# qPCR_pcb_breakout_AD630ARZ.net
KiCad netlist of a schematic drawn in EAGLE
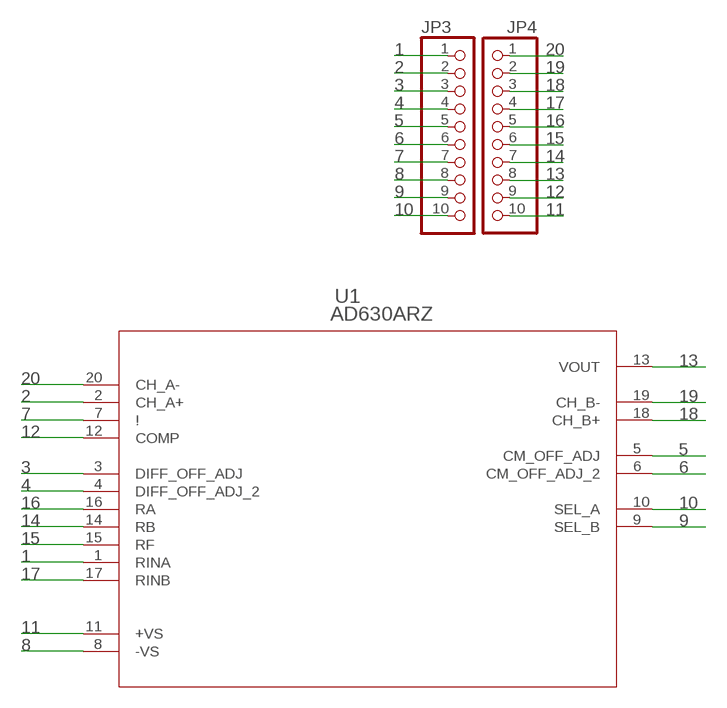
[diagram p0: schematic, sheet 1]

(export (version "E")
  (design (tool "Eeschema 10.0.6"))
  (components
    (comp (ref "JP3")
      (value "PINHD-1X10")
      (footprint "eagle-import:1X10")
      (libsource (lib "eagle-import") (part "PINHD-1X10"))
    )
    (comp (ref "JP4")
      (value "PINHD-1X10")
      (footprint "eagle-import:1X10")
      (libsource (lib "eagle-import") (part "PINHD-1X10"))
    )
    (comp (ref "U1")
      (value "AD630ARZ")
      (footprint "eagle-import:RW_20_ADI")
      (libsource (lib "eagle-import") (part "AD630ARZ"))
    )
  )
  (nets
    (net (code "1") (name "/1") (class "Default")
      (node (ref "JP3") (pin "1") (pinfunction "1_1") (pintype "passive"))
      (node (ref "U1") (pin "1") (pinfunction "RINA_1") (pintype "passive"))
    )
    (net (code "2") (name "/2") (class "Default")
      (node (ref "JP3") (pin "2") (pinfunction "2_2") (pintype "passive"))
      (node (ref "U1") (pin "2") (pinfunction "CH_A+_2") (pintype "passive"))
    )
    (net (code "3") (name "/3") (class "Default")
      (node (ref "JP3") (pin "3") (pinfunction "3_3") (pintype "passive"))
      (node (ref "U1") (pin "3") (pinfunction "DIFF_OFF_ADJ_3") (pintype "passive"))
    )
    (net (code "4") (name "/4") (class "Default")
      (node (ref "JP3") (pin "4") (pinfunction "4_4") (pintype "passive"))
      (node (ref "U1") (pin "4") (pinfunction "DIFF_OFF_ADJ_2_4") (pintype "passive"))
    )
    (net (code "5") (name "/5") (class "Default")
      (node (ref "JP3") (pin "5") (pinfunction "5_5") (pintype "passive"))
      (node (ref "U1") (pin "5") (pinfunction "CM_OFF_ADJ_5") (pintype "passive"))
    )
    (net (code "6") (name "/6") (class "Default")
      (node (ref "JP3") (pin "6") (pinfunction "6_6") (pintype "passive"))
      (node (ref "U1") (pin "6") (pinfunction "CM_OFF_ADJ_2_6") (pintype "passive"))
    )
    (net (code "7") (name "/7") (class "Default")
      (node (ref "JP3") (pin "7") (pinfunction "7_7") (pintype "passive"))
      (node (ref "U1") (pin "7") (pinfunction "~_7") (pintype "passive"))
    )
    (net (code "8") (name "/8") (class "Default")
      (node (ref "JP3") (pin "8") (pinfunction "8_8") (pintype "passive"))
      (node (ref "U1") (pin "8") (pinfunction "-VS_8") (pintype "power_in"))
    )
    (net (code "9") (name "/9") (class "Default")
      (node (ref "JP3") (pin "9") (pinfunction "9_9") (pintype "passive"))
      (node (ref "U1") (pin "9") (pinfunction "SEL_B_9") (pintype "passive"))
    )
    (net (code "10") (name "/10") (class "Default")
      (node (ref "JP3") (pin "10") (pinfunction "10_10") (pintype "passive"))
      (node (ref "U1") (pin "10") (pinfunction "SEL_A_10") (pintype "passive"))
    )
    (net (code "11") (name "/11") (class "Default")
      (node (ref "JP4") (pin "10") (pinfunction "10_10") (pintype "passive"))
      (node (ref "U1") (pin "11") (pinfunction "+VS_11") (pintype "power_in"))
    )
    (net (code "12") (name "/12") (class "Default")
      (node (ref "JP4") (pin "9") (pinfunction "9_9") (pintype "passive"))
      (node (ref "U1") (pin "12") (pinfunction "COMP_12") (pintype "passive"))
    )
    (net (code "13") (name "/13") (class "Default")
      (node (ref "JP4") (pin "8") (pinfunction "8_8") (pintype "passive"))
      (node (ref "U1") (pin "13") (pinfunction "VOUT_13") (pintype "passive"))
    )
    (net (code "14") (name "/14") (class "Default")
      (node (ref "JP4") (pin "7") (pinfunction "7_7") (pintype "passive"))
      (node (ref "U1") (pin "14") (pinfunction "RB_14") (pintype "passive"))
    )
    (net (code "15") (name "/15") (class "Default")
      (node (ref "JP4") (pin "6") (pinfunction "6_6") (pintype "passive"))
      (node (ref "U1") (pin "15") (pinfunction "RF_15") (pintype "passive"))
    )
    (net (code "16") (name "/16") (class "Default")
      (node (ref "JP4") (pin "5") (pinfunction "5_5") (pintype "passive"))
      (node (ref "U1") (pin "16") (pinfunction "RA_16") (pintype "passive"))
    )
    (net (code "17") (name "/17") (class "Default")
      (node (ref "JP4") (pin "4") (pinfunction "4_4") (pintype "passive"))
      (node (ref "U1") (pin "17") (pinfunction "RINB_17") (pintype "passive"))
    )
    (net (code "18") (name "/18") (class "Default")
      (node (ref "JP4") (pin "3") (pinfunction "3_3") (pintype "passive"))
      (node (ref "U1") (pin "18") (pinfunction "CH_B+_18") (pintype "passive"))
    )
    (net (code "19") (name "/19") (class "Default")
      (node (ref "JP4") (pin "2") (pinfunction "2_2") (pintype "passive"))
      (node (ref "U1") (pin "19") (pinfunction "CH_B-_19") (pintype "passive"))
    )
    (net (code "20") (name "/20") (class "Default")
      (node (ref "JP4") (pin "1") (pinfunction "1_1") (pintype "passive"))
      (node (ref "U1") (pin "20") (pinfunction "CH_A-_20") (pintype "passive"))
    )
  )
)
